# DeMux.net
KiCad netlist of a schematic drawn in EAGLE
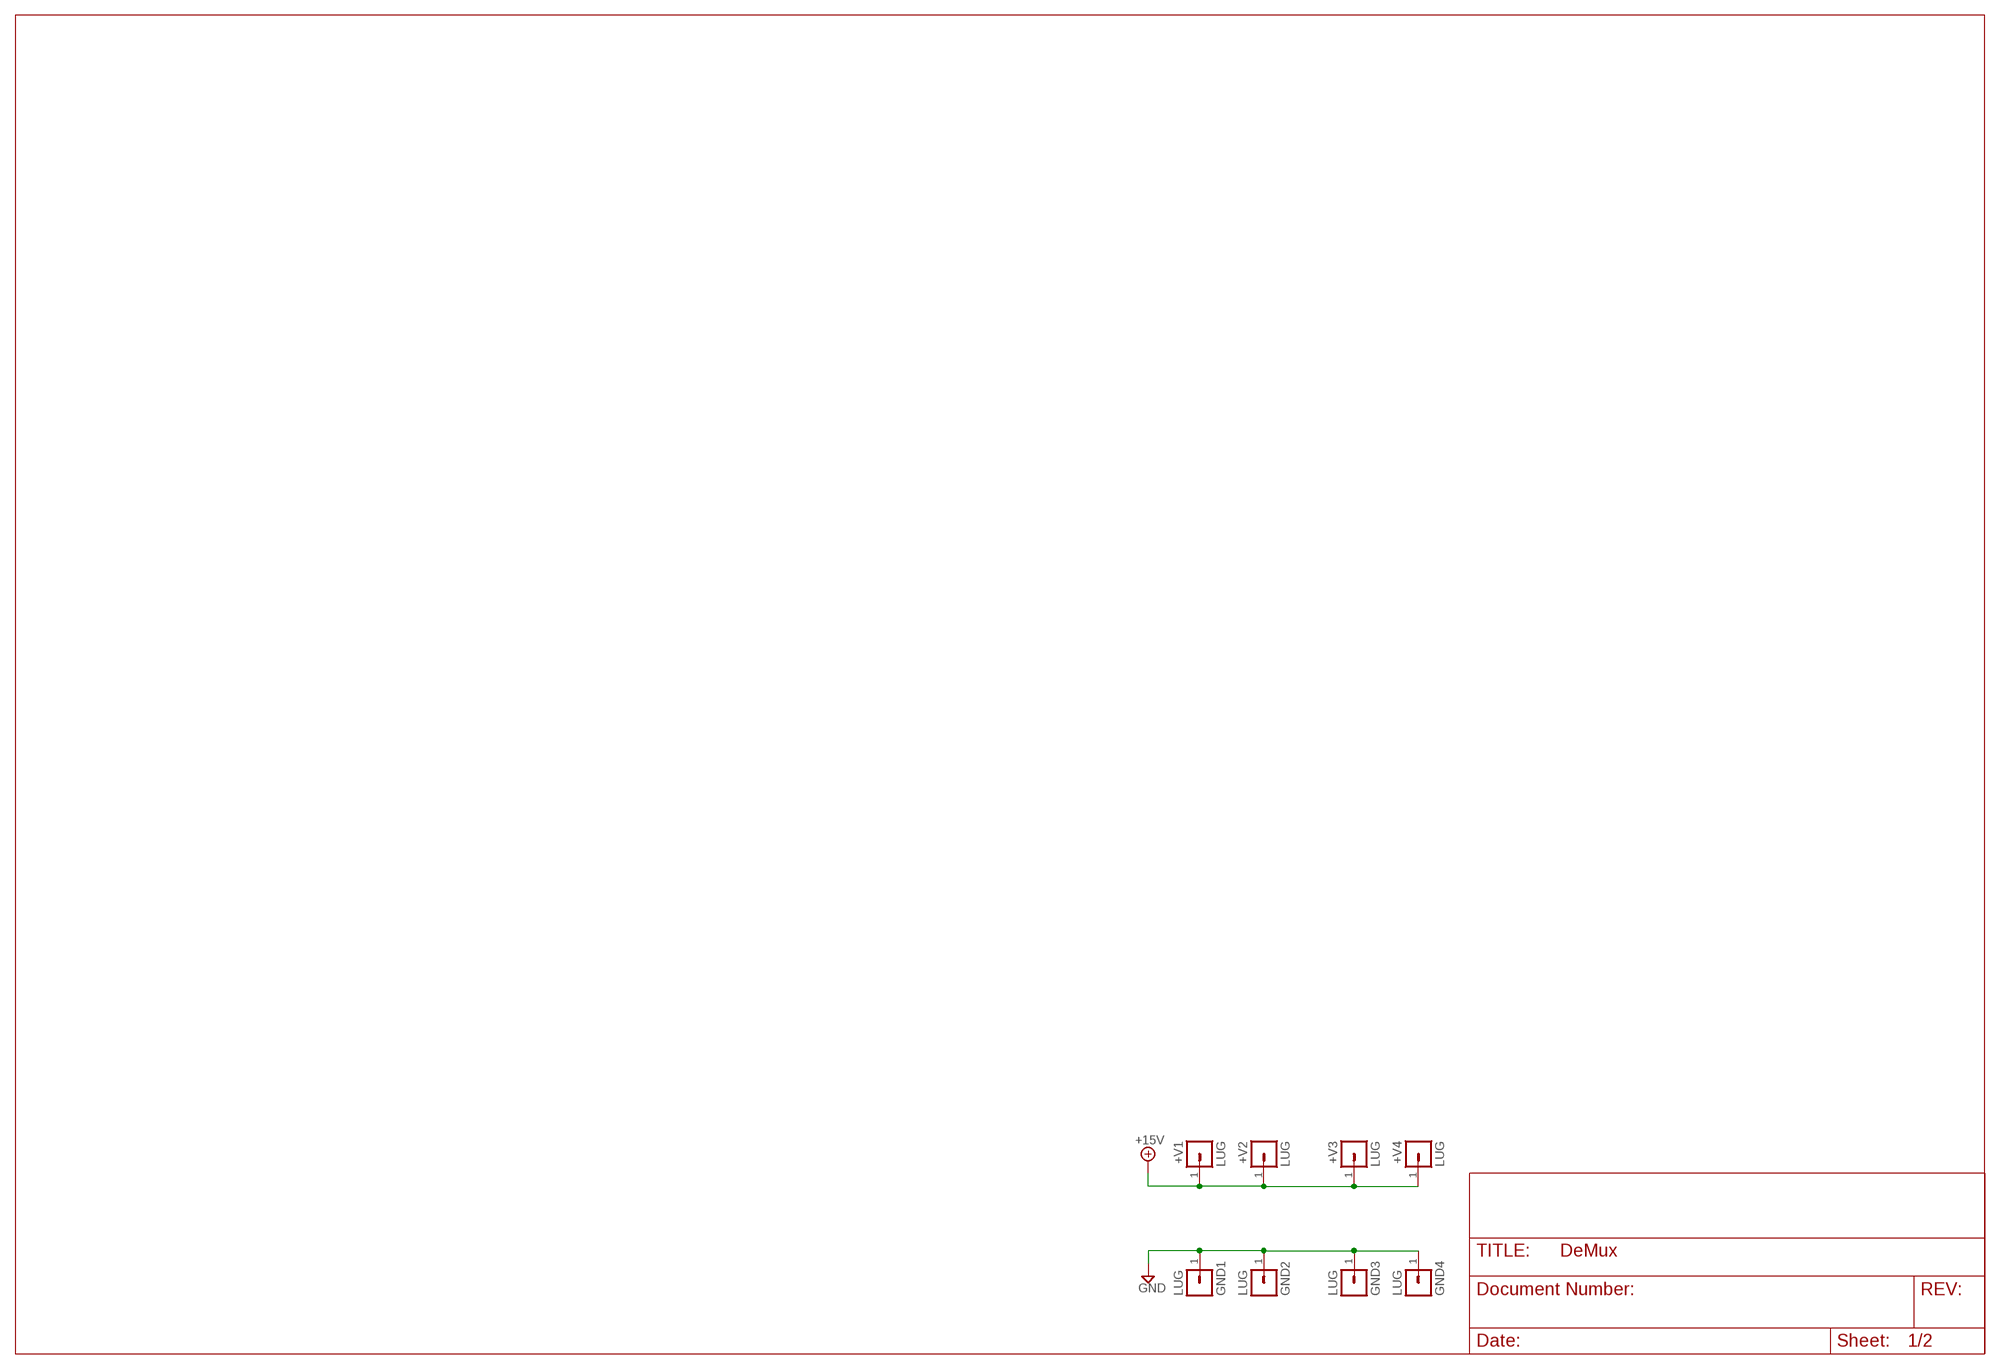
[diagram p0: schematic, sheet 1]
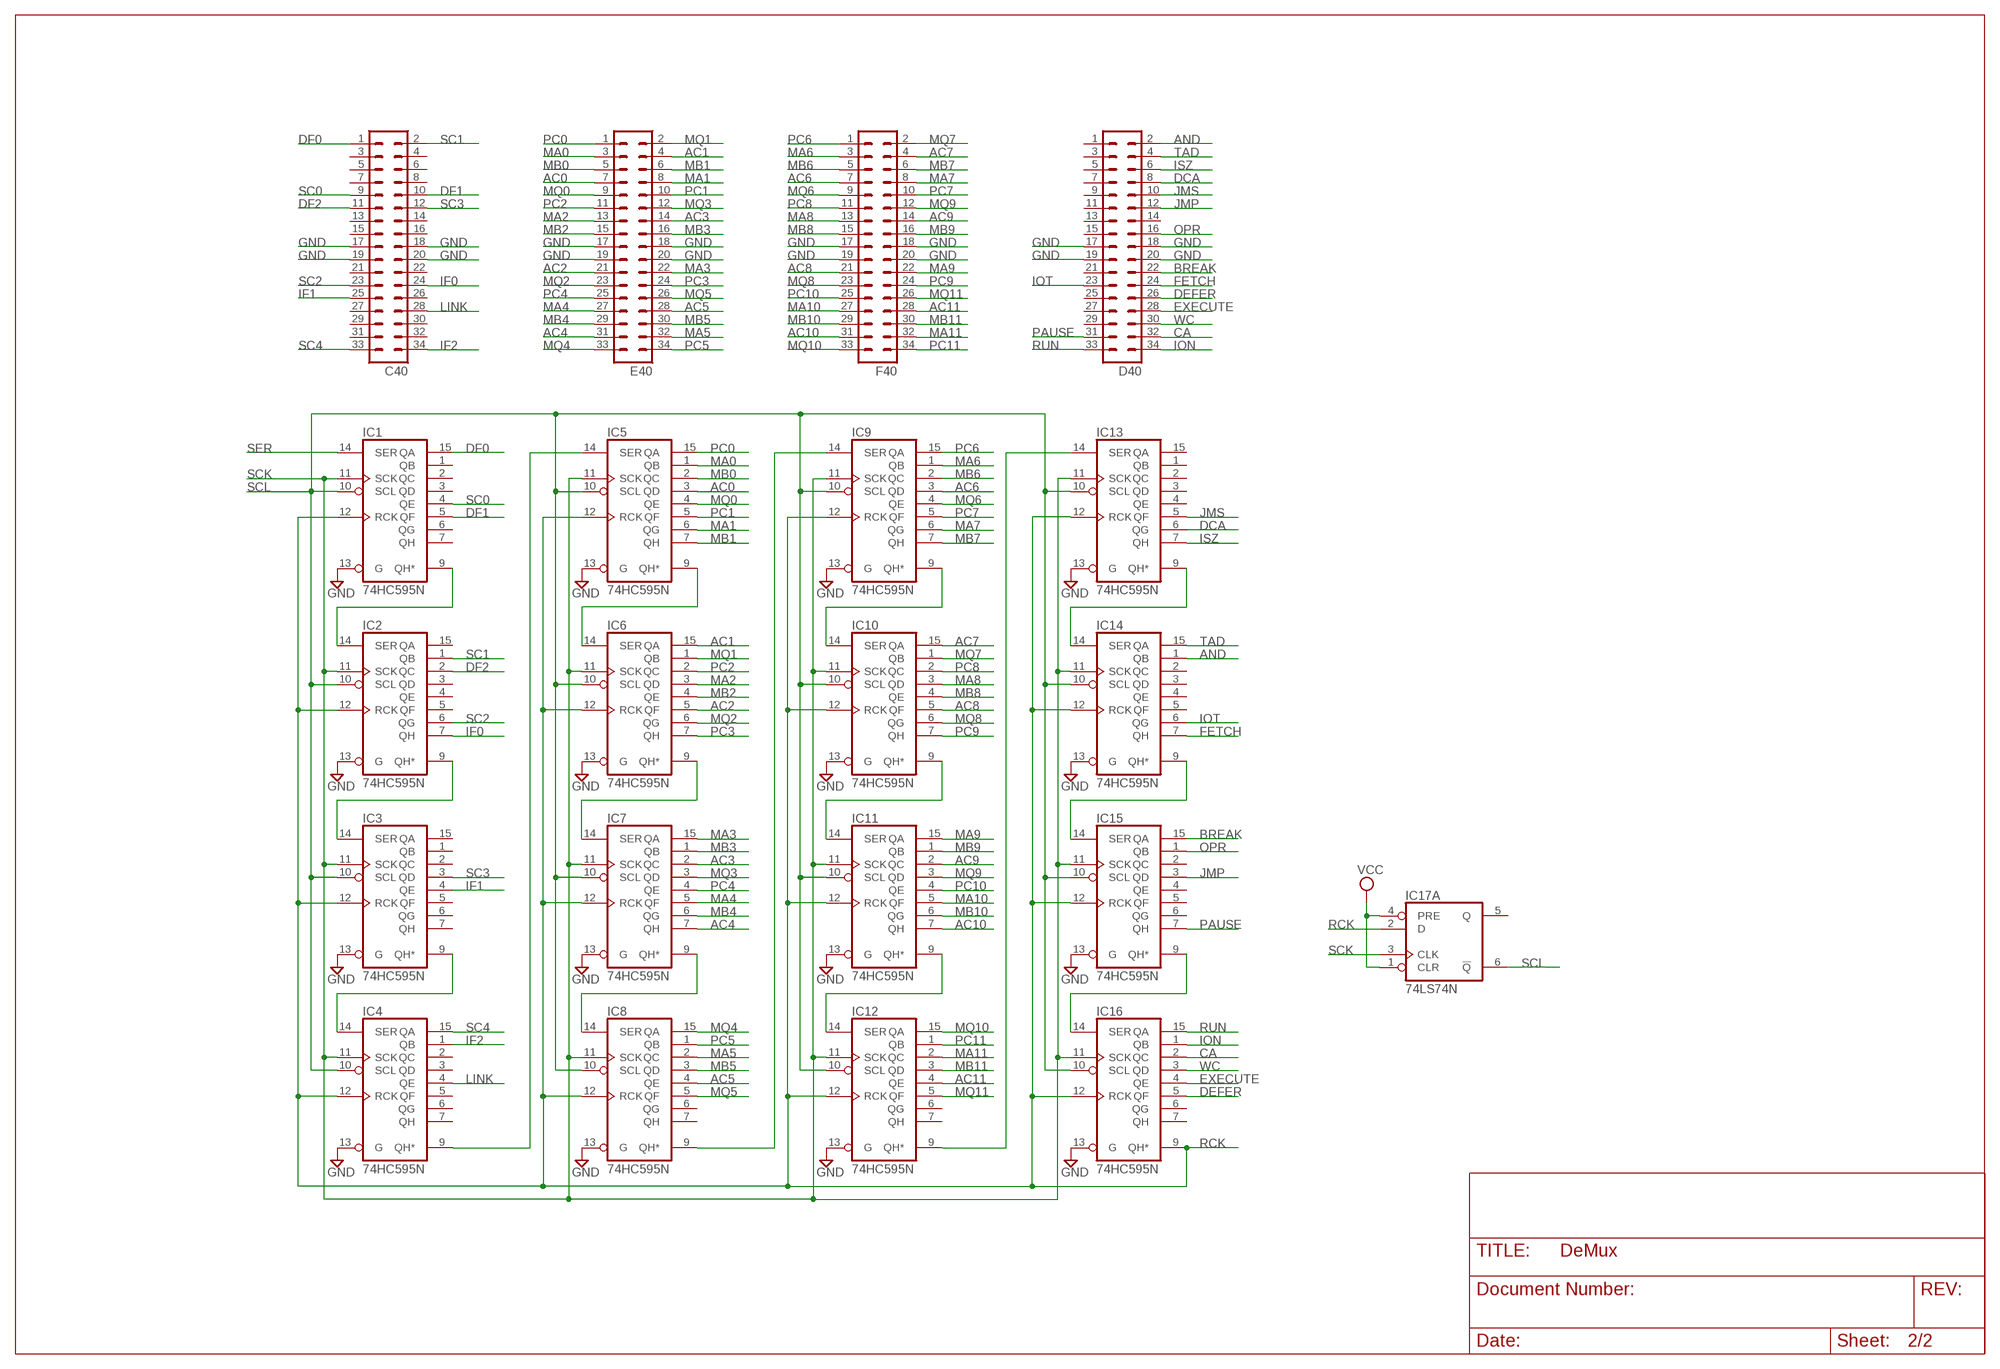
[diagram p1: schematic, sheet 2]

(export (version "E")
  (design (tool "Eeschema 10.0.6"))
  (components
    (comp (ref "+V1")
      (value "LUG")
      (footprint "eagle-import:SPADELUG")
      (libsource (lib "eagle-import") (part "LUG"))
    )
    (comp (ref "+V2")
      (value "LUG")
      (footprint "eagle-import:SPADELUG")
      (libsource (lib "eagle-import") (part "LUG"))
    )
    (comp (ref "+V3")
      (value "LUG")
      (footprint "eagle-import:SPADELUG")
      (libsource (lib "eagle-import") (part "LUG"))
    )
    (comp (ref "+V4")
      (value "LUG")
      (footprint "eagle-import:SPADELUG")
      (libsource (lib "eagle-import") (part "LUG"))
    )
    (comp (ref "GND1")
      (value "LUG")
      (footprint "eagle-import:SPADELUG")
      (libsource (lib "eagle-import") (part "LUG"))
    )
    (comp (ref "GND2")
      (value "LUG")
      (footprint "eagle-import:SPADELUG")
      (libsource (lib "eagle-import") (part "LUG"))
    )
    (comp (ref "GND3")
      (value "LUG")
      (footprint "eagle-import:SPADELUG")
      (libsource (lib "eagle-import") (part "LUG"))
    )
    (comp (ref "GND4")
      (value "LUG")
      (footprint "eagle-import:SPADELUG")
      (libsource (lib "eagle-import") (part "LUG"))
    )
    (comp (ref "C40")
      (value "MA17-2")
      (footprint "eagle-import:MA17-2")
      (libsource (lib "eagle-import") (part "MA17-2"))
    )
    (comp (ref "D40")
      (value "MA17-2")
      (footprint "eagle-import:MA17-2")
      (libsource (lib "eagle-import") (part "MA17-2"))
    )
    (comp (ref "E40")
      (value "MA17-2")
      (footprint "eagle-import:MA17-2")
      (libsource (lib "eagle-import") (part "MA17-2"))
    )
    (comp (ref "F40")
      (value "MA17-2")
      (footprint "eagle-import:MA17-2")
      (libsource (lib "eagle-import") (part "MA17-2"))
    )
    (comp (ref "IC1")
      (value "74HC595N")
      (footprint "eagle-import:DIL16")
      (libsource (lib "eagle-import") (part "74595NLS"))
    )
    (comp (ref "IC2")
      (value "74HC595N")
      (footprint "eagle-import:DIL16")
      (libsource (lib "eagle-import") (part "74595NLS"))
    )
    (comp (ref "IC3")
      (value "74HC595N")
      (footprint "eagle-import:DIL16")
      (libsource (lib "eagle-import") (part "74595NLS"))
    )
    (comp (ref "IC4")
      (value "74HC595N")
      (footprint "eagle-import:DIL16")
      (libsource (lib "eagle-import") (part "74595NLS"))
    )
    (comp (ref "IC5")
      (value "74HC595N")
      (footprint "eagle-import:DIL16")
      (libsource (lib "eagle-import") (part "74595NLS"))
    )
    (comp (ref "IC6")
      (value "74HC595N")
      (footprint "eagle-import:DIL16")
      (libsource (lib "eagle-import") (part "74595NLS"))
    )
    (comp (ref "IC7")
      (value "74HC595N")
      (footprint "eagle-import:DIL16")
      (libsource (lib "eagle-import") (part "74595NLS"))
    )
    (comp (ref "IC8")
      (value "74HC595N")
      (footprint "eagle-import:DIL16")
      (libsource (lib "eagle-import") (part "74595NLS"))
    )
    (comp (ref "IC9")
      (value "74HC595N")
      (footprint "eagle-import:DIL16")
      (libsource (lib "eagle-import") (part "74595NLS"))
    )
    (comp (ref "IC10")
      (value "74HC595N")
      (footprint "eagle-import:DIL16")
      (libsource (lib "eagle-import") (part "74595NLS"))
    )
    (comp (ref "IC11")
      (value "74HC595N")
      (footprint "eagle-import:DIL16")
      (libsource (lib "eagle-import") (part "74595NLS"))
    )
    (comp (ref "IC12")
      (value "74HC595N")
      (footprint "eagle-import:DIL16")
      (libsource (lib "eagle-import") (part "74595NLS"))
    )
    (comp (ref "IC13")
      (value "74HC595N")
      (footprint "eagle-import:DIL16")
      (libsource (lib "eagle-import") (part "74595NLS"))
    )
    (comp (ref "IC14")
      (value "74HC595N")
      (footprint "eagle-import:DIL16")
      (libsource (lib "eagle-import") (part "74595NLS"))
    )
    (comp (ref "IC15")
      (value "74HC595N")
      (footprint "eagle-import:DIL16")
      (libsource (lib "eagle-import") (part "74595NLS"))
    )
    (comp (ref "IC16")
      (value "74HC595N")
      (footprint "eagle-import:DIL16")
      (libsource (lib "eagle-import") (part "74595NLS"))
    )
    (comp (ref "IC17")
      (value "74LS74N")
      (footprint "eagle-import:DIL14")
      (libsource (lib "eagle-import") (part "7474NLS"))
    )
  )
  (nets
    (net (code "1") (name "+15V") (class "Default")
      (node (ref "+V1") (pin "1") (pinfunction "1_1") (pintype "passive"))
      (node (ref "+V2") (pin "1") (pinfunction "1_1") (pintype "passive"))
      (node (ref "+V3") (pin "1") (pinfunction "1_1") (pintype "passive"))
      (node (ref "+V4") (pin "1") (pinfunction "1_1") (pintype "passive"))
    )
    (net (code "2") (name "AC0") (class "Default")
      (node (ref "E40") (pin "7") (pinfunction "7_7") (pintype "passive"))
      (node (ref "IC5") (pin "3") (pinfunction "QD_3") (pintype "tri_state"))
    )
    (net (code "3") (name "AC1") (class "Default")
      (node (ref "E40") (pin "4") (pinfunction "4_4") (pintype "passive"))
      (node (ref "IC6") (pin "15") (pinfunction "QA_15") (pintype "tri_state"))
    )
    (net (code "4") (name "AC2") (class "Default")
      (node (ref "E40") (pin "21") (pinfunction "21_21") (pintype "passive"))
      (node (ref "IC6") (pin "5") (pinfunction "QF_5") (pintype "tri_state"))
    )
    (net (code "5") (name "AC3") (class "Default")
      (node (ref "E40") (pin "14") (pinfunction "14_14") (pintype "passive"))
      (node (ref "IC7") (pin "2") (pinfunction "QC_2") (pintype "tri_state"))
    )
    (net (code "6") (name "AC4") (class "Default")
      (node (ref "E40") (pin "31") (pinfunction "31_31") (pintype "passive"))
      (node (ref "IC7") (pin "7") (pinfunction "QH_7") (pintype "tri_state"))
    )
    (net (code "7") (name "AC5") (class "Default")
      (node (ref "E40") (pin "28") (pinfunction "28_28") (pintype "passive"))
      (node (ref "IC8") (pin "4") (pinfunction "QE_4") (pintype "tri_state"))
    )
    (net (code "8") (name "AC6") (class "Default")
      (node (ref "F40") (pin "7") (pinfunction "7_7") (pintype "passive"))
      (node (ref "IC9") (pin "3") (pinfunction "QD_3") (pintype "tri_state"))
    )
    (net (code "9") (name "AC7") (class "Default")
      (node (ref "F40") (pin "4") (pinfunction "4_4") (pintype "passive"))
      (node (ref "IC10") (pin "15") (pinfunction "QA_15") (pintype "tri_state"))
    )
    (net (code "10") (name "AC8") (class "Default")
      (node (ref "F40") (pin "21") (pinfunction "21_21") (pintype "passive"))
      (node (ref "IC10") (pin "5") (pinfunction "QF_5") (pintype "tri_state"))
    )
    (net (code "11") (name "AC9") (class "Default")
      (node (ref "F40") (pin "14") (pinfunction "14_14") (pintype "passive"))
      (node (ref "IC11") (pin "2") (pinfunction "QC_2") (pintype "tri_state"))
    )
    (net (code "12") (name "AC10") (class "Default")
      (node (ref "F40") (pin "31") (pinfunction "31_31") (pintype "passive"))
      (node (ref "IC11") (pin "7") (pinfunction "QH_7") (pintype "tri_state"))
    )
    (net (code "13") (name "AC11") (class "Default")
      (node (ref "F40") (pin "28") (pinfunction "28_28") (pintype "passive"))
      (node (ref "IC12") (pin "4") (pinfunction "QE_4") (pintype "tri_state"))
    )
    (net (code "14") (name "AND") (class "Default")
      (node (ref "D40") (pin "2") (pinfunction "2_2") (pintype "passive"))
      (node (ref "IC14") (pin "1") (pinfunction "QB_1") (pintype "tri_state"))
    )
    (net (code "15") (name "BREAK") (class "Default")
      (node (ref "D40") (pin "22") (pinfunction "22_22") (pintype "passive"))
      (node (ref "IC15") (pin "15") (pinfunction "QA_15") (pintype "tri_state"))
    )
    (net (code "16") (name "CA") (class "Default")
      (node (ref "D40") (pin "32") (pinfunction "32_32") (pintype "passive"))
      (node (ref "IC16") (pin "2") (pinfunction "QC_2") (pintype "tri_state"))
    )
    (net (code "17") (name "DCA") (class "Default")
      (node (ref "D40") (pin "8") (pinfunction "8_8") (pintype "passive"))
      (node (ref "IC13") (pin "6") (pinfunction "QG_6") (pintype "tri_state"))
    )
    (net (code "18") (name "DEFER") (class "Default")
      (node (ref "D40") (pin "26") (pinfunction "26_26") (pintype "passive"))
      (node (ref "IC16") (pin "5") (pinfunction "QF_5") (pintype "tri_state"))
    )
    (net (code "19") (name "DF0") (class "Default")
      (node (ref "C40") (pin "1") (pinfunction "1_1") (pintype "passive"))
      (node (ref "IC1") (pin "15") (pinfunction "QA_15") (pintype "tri_state"))
    )
    (net (code "20") (name "DF1") (class "Default")
      (node (ref "C40") (pin "10") (pinfunction "10_10") (pintype "passive"))
      (node (ref "IC1") (pin "5") (pinfunction "QF_5") (pintype "tri_state"))
    )
    (net (code "21") (name "DF2") (class "Default")
      (node (ref "C40") (pin "11") (pinfunction "11_11") (pintype "passive"))
      (node (ref "IC2") (pin "2") (pinfunction "QC_2") (pintype "tri_state"))
    )
    (net (code "22") (name "EXECUTE") (class "Default")
      (node (ref "D40") (pin "28") (pinfunction "28_28") (pintype "passive"))
      (node (ref "IC16") (pin "4") (pinfunction "QE_4") (pintype "tri_state"))
    )
    (net (code "23") (name "FETCH") (class "Default")
      (node (ref "D40") (pin "24") (pinfunction "24_24") (pintype "passive"))
      (node (ref "IC14") (pin "7") (pinfunction "QH_7") (pintype "tri_state"))
    )
    (net (code "24") (name "GND") (class "Default")
      (node (ref "C40") (pin "17") (pinfunction "17_17") (pintype "passive"))
      (node (ref "C40") (pin "18") (pinfunction "18_18") (pintype "passive"))
      (node (ref "C40") (pin "19") (pinfunction "19_19") (pintype "passive"))
      (node (ref "C40") (pin "20") (pinfunction "20_20") (pintype "passive"))
      (node (ref "D40") (pin "17") (pinfunction "17_17") (pintype "passive"))
      (node (ref "D40") (pin "18") (pinfunction "18_18") (pintype "passive"))
      (node (ref "D40") (pin "19") (pinfunction "19_19") (pintype "passive"))
      (node (ref "D40") (pin "20") (pinfunction "20_20") (pintype "passive"))
      (node (ref "E40") (pin "17") (pinfunction "17_17") (pintype "passive"))
      (node (ref "E40") (pin "18") (pinfunction "18_18") (pintype "passive"))
      (node (ref "E40") (pin "19") (pinfunction "19_19") (pintype "passive"))
      (node (ref "E40") (pin "20") (pinfunction "20_20") (pintype "passive"))
      (node (ref "F40") (pin "17") (pinfunction "17_17") (pintype "passive"))
      (node (ref "F40") (pin "18") (pinfunction "18_18") (pintype "passive"))
      (node (ref "F40") (pin "19") (pinfunction "19_19") (pintype "passive"))
      (node (ref "F40") (pin "20") (pinfunction "20_20") (pintype "passive"))
      (node (ref "GND1") (pin "1") (pinfunction "1_1") (pintype "passive"))
      (node (ref "GND2") (pin "1") (pinfunction "1_1") (pintype "passive"))
      (node (ref "GND3") (pin "1") (pinfunction "1_1") (pintype "passive"))
      (node (ref "GND4") (pin "1") (pinfunction "1_1") (pintype "passive"))
      (node (ref "IC1") (pin "13") (pinfunction "G_13") (pintype "input"))
      (node (ref "IC10") (pin "13") (pinfunction "G_13") (pintype "input"))
      (node (ref "IC11") (pin "13") (pinfunction "G_13") (pintype "input"))
      (node (ref "IC12") (pin "13") (pinfunction "G_13") (pintype "input"))
      (node (ref "IC13") (pin "13") (pinfunction "G_13") (pintype "input"))
      (node (ref "IC14") (pin "13") (pinfunction "G_13") (pintype "input"))
      (node (ref "IC15") (pin "13") (pinfunction "G_13") (pintype "input"))
      (node (ref "IC16") (pin "13") (pinfunction "G_13") (pintype "input"))
      (node (ref "IC2") (pin "13") (pinfunction "G_13") (pintype "input"))
      (node (ref "IC3") (pin "13") (pinfunction "G_13") (pintype "input"))
      (node (ref "IC4") (pin "13") (pinfunction "G_13") (pintype "input"))
      (node (ref "IC5") (pin "13") (pinfunction "G_13") (pintype "input"))
      (node (ref "IC6") (pin "13") (pinfunction "G_13") (pintype "input"))
      (node (ref "IC7") (pin "13") (pinfunction "G_13") (pintype "input"))
      (node (ref "IC8") (pin "13") (pinfunction "G_13") (pintype "input"))
      (node (ref "IC9") (pin "13") (pinfunction "G_13") (pintype "input"))
    )
    (net (code "25") (name "IF0") (class "Default")
      (node (ref "C40") (pin "24") (pinfunction "24_24") (pintype "passive"))
      (node (ref "IC2") (pin "7") (pinfunction "QH_7") (pintype "tri_state"))
    )
    (net (code "26") (name "IF1") (class "Default")
      (node (ref "C40") (pin "25") (pinfunction "25_25") (pintype "passive"))
      (node (ref "IC3") (pin "4") (pinfunction "QE_4") (pintype "tri_state"))
    )
    (net (code "27") (name "IF2") (class "Default")
      (node (ref "C40") (pin "34") (pinfunction "34_34") (pintype "passive"))
      (node (ref "IC4") (pin "1") (pinfunction "QB_1") (pintype "tri_state"))
    )
    (net (code "28") (name "ION") (class "Default")
      (node (ref "D40") (pin "34") (pinfunction "34_34") (pintype "passive"))
      (node (ref "IC16") (pin "1") (pinfunction "QB_1") (pintype "tri_state"))
    )
    (net (code "29") (name "IOT") (class "Default")
      (node (ref "D40") (pin "23") (pinfunction "23_23") (pintype "passive"))
      (node (ref "IC14") (pin "6") (pinfunction "QG_6") (pintype "tri_state"))
    )
    (net (code "30") (name "ISZ") (class "Default")
      (node (ref "D40") (pin "6") (pinfunction "6_6") (pintype "passive"))
      (node (ref "IC13") (pin "7") (pinfunction "QH_7") (pintype "tri_state"))
    )
    (net (code "31") (name "JMP") (class "Default")
      (node (ref "D40") (pin "12") (pinfunction "12_12") (pintype "passive"))
      (node (ref "IC15") (pin "3") (pinfunction "QD_3") (pintype "tri_state"))
    )
    (net (code "32") (name "JMS") (class "Default")
      (node (ref "D40") (pin "10") (pinfunction "10_10") (pintype "passive"))
      (node (ref "IC13") (pin "5") (pinfunction "QF_5") (pintype "tri_state"))
    )
    (net (code "33") (name "LINK") (class "Default")
      (node (ref "C40") (pin "28") (pinfunction "28_28") (pintype "passive"))
      (node (ref "IC4") (pin "4") (pinfunction "QE_4") (pintype "tri_state"))
    )
    (net (code "34") (name "MA0") (class "Default")
      (node (ref "E40") (pin "3") (pinfunction "3_3") (pintype "passive"))
      (node (ref "IC5") (pin "1") (pinfunction "QB_1") (pintype "tri_state"))
    )
    (net (code "35") (name "MA1") (class "Default")
      (node (ref "E40") (pin "8") (pinfunction "8_8") (pintype "passive"))
      (node (ref "IC5") (pin "6") (pinfunction "QG_6") (pintype "tri_state"))
    )
    (net (code "36") (name "MA2") (class "Default")
      (node (ref "E40") (pin "13") (pinfunction "13_13") (pintype "passive"))
      (node (ref "IC6") (pin "3") (pinfunction "QD_3") (pintype "tri_state"))
    )
    (net (code "37") (name "MA3") (class "Default")
      (node (ref "E40") (pin "22") (pinfunction "22_22") (pintype "passive"))
      (node (ref "IC7") (pin "15") (pinfunction "QA_15") (pintype "tri_state"))
    )
    (net (code "38") (name "MA4") (class "Default")
      (node (ref "E40") (pin "27") (pinfunction "27_27") (pintype "passive"))
      (node (ref "IC7") (pin "5") (pinfunction "QF_5") (pintype "tri_state"))
    )
    (net (code "39") (name "MA5") (class "Default")
      (node (ref "E40") (pin "32") (pinfunction "32_32") (pintype "passive"))
      (node (ref "IC8") (pin "2") (pinfunction "QC_2") (pintype "tri_state"))
    )
    (net (code "40") (name "MA6") (class "Default")
      (node (ref "F40") (pin "3") (pinfunction "3_3") (pintype "passive"))
      (node (ref "IC9") (pin "1") (pinfunction "QB_1") (pintype "tri_state"))
    )
    (net (code "41") (name "MA7") (class "Default")
      (node (ref "F40") (pin "8") (pinfunction "8_8") (pintype "passive"))
      (node (ref "IC9") (pin "6") (pinfunction "QG_6") (pintype "tri_state"))
    )
    (net (code "42") (name "MA8") (class "Default")
      (node (ref "F40") (pin "13") (pinfunction "13_13") (pintype "passive"))
      (node (ref "IC10") (pin "3") (pinfunction "QD_3") (pintype "tri_state"))
    )
    (net (code "43") (name "MA9") (class "Default")
      (node (ref "F40") (pin "22") (pinfunction "22_22") (pintype "passive"))
      (node (ref "IC11") (pin "15") (pinfunction "QA_15") (pintype "tri_state"))
    )
    (net (code "44") (name "MA10") (class "Default")
      (node (ref "F40") (pin "27") (pinfunction "27_27") (pintype "passive"))
      (node (ref "IC11") (pin "5") (pinfunction "QF_5") (pintype "tri_state"))
    )
    (net (code "45") (name "MA11") (class "Default")
      (node (ref "F40") (pin "32") (pinfunction "32_32") (pintype "passive"))
      (node (ref "IC12") (pin "2") (pinfunction "QC_2") (pintype "tri_state"))
    )
    (net (code "46") (name "MB0") (class "Default")
      (node (ref "E40") (pin "5") (pinfunction "5_5") (pintype "passive"))
      (node (ref "IC5") (pin "2") (pinfunction "QC_2") (pintype "tri_state"))
    )
    (net (code "47") (name "MB1") (class "Default")
      (node (ref "E40") (pin "6") (pinfunction "6_6") (pintype "passive"))
      (node (ref "IC5") (pin "7") (pinfunction "QH_7") (pintype "tri_state"))
    )
    (net (code "48") (name "MB2") (class "Default")
      (node (ref "E40") (pin "15") (pinfunction "15_15") (pintype "passive"))
      (node (ref "IC6") (pin "4") (pinfunction "QE_4") (pintype "tri_state"))
    )
    (net (code "49") (name "MB3") (class "Default")
      (node (ref "E40") (pin "16") (pinfunction "16_16") (pintype "passive"))
      (node (ref "IC7") (pin "1") (pinfunction "QB_1") (pintype "tri_state"))
    )
    (net (code "50") (name "MB4") (class "Default")
      (node (ref "E40") (pin "29") (pinfunction "29_29") (pintype "passive"))
      (node (ref "IC7") (pin "6") (pinfunction "QG_6") (pintype "tri_state"))
    )
    (net (code "51") (name "MB5") (class "Default")
      (node (ref "E40") (pin "30") (pinfunction "30_30") (pintype "passive"))
      (node (ref "IC8") (pin "3") (pinfunction "QD_3") (pintype "tri_state"))
    )
    (net (code "52") (name "MB6") (class "Default")
      (node (ref "F40") (pin "5") (pinfunction "5_5") (pintype "passive"))
      (node (ref "IC9") (pin "2") (pinfunction "QC_2") (pintype "tri_state"))
    )
    (net (code "53") (name "MB7") (class "Default")
      (node (ref "F40") (pin "6") (pinfunction "6_6") (pintype "passive"))
      (node (ref "IC9") (pin "7") (pinfunction "QH_7") (pintype "tri_state"))
    )
    (net (code "54") (name "MB8") (class "Default")
      (node (ref "F40") (pin "15") (pinfunction "15_15") (pintype "passive"))
      (node (ref "IC10") (pin "4") (pinfunction "QE_4") (pintype "tri_state"))
    )
    (net (code "55") (name "MB9") (class "Default")
      (node (ref "F40") (pin "16") (pinfunction "16_16") (pintype "passive"))
      (node (ref "IC11") (pin "1") (pinfunction "QB_1") (pintype "tri_state"))
    )
    (net (code "56") (name "MB10") (class "Default")
      (node (ref "F40") (pin "29") (pinfunction "29_29") (pintype "passive"))
      (node (ref "IC11") (pin "6") (pinfunction "QG_6") (pintype "tri_state"))
    )
    (net (code "57") (name "MB11") (class "Default")
      (node (ref "F40") (pin "30") (pinfunction "30_30") (pintype "passive"))
      (node (ref "IC12") (pin "3") (pinfunction "QD_3") (pintype "tri_state"))
    )
    (net (code "58") (name "MQ0") (class "Default")
      (node (ref "E40") (pin "9") (pinfunction "9_9") (pintype "passive"))
      (node (ref "IC5") (pin "4") (pinfunction "QE_4") (pintype "tri_state"))
    )
    (net (code "59") (name "MQ1") (class "Default")
      (node (ref "E40") (pin "2") (pinfunction "2_2") (pintype "passive"))
      (node (ref "IC6") (pin "1") (pinfunction "QB_1") (pintype "tri_state"))
    )
    (net (code "60") (name "MQ2") (class "Default")
      (node (ref "E40") (pin "23") (pinfunction "23_23") (pintype "passive"))
      (node (ref "IC6") (pin "6") (pinfunction "QG_6") (pintype "tri_state"))
    )
    (net (code "61") (name "MQ3") (class "Default")
      (node (ref "E40") (pin "12") (pinfunction "12_12") (pintype "passive"))
      (node (ref "IC7") (pin "3") (pinfunction "QD_3") (pintype "tri_state"))
    )
    (net (code "62") (name "MQ4") (class "Default")
      (node (ref "E40") (pin "33") (pinfunction "33_33") (pintype "passive"))
      (node (ref "IC8") (pin "15") (pinfunction "QA_15") (pintype "tri_state"))
    )
    (net (code "63") (name "MQ5") (class "Default")
      (node (ref "E40") (pin "26") (pinfunction "26_26") (pintype "passive"))
      (node (ref "IC8") (pin "5") (pinfunction "QF_5") (pintype "tri_state"))
    )
    (net (code "64") (name "MQ6") (class "Default")
      (node (ref "F40") (pin "9") (pinfunction "9_9") (pintype "passive"))
      (node (ref "IC9") (pin "4") (pinfunction "QE_4") (pintype "tri_state"))
    )
    (net (code "65") (name "MQ7") (class "Default")
      (node (ref "F40") (pin "2") (pinfunction "2_2") (pintype "passive"))
      (node (ref "IC10") (pin "1") (pinfunction "QB_1") (pintype "tri_state"))
    )
    (net (code "66") (name "MQ8") (class "Default")
      (node (ref "F40") (pin "23") (pinfunction "23_23") (pintype "passive"))
      (node (ref "IC10") (pin "6") (pinfunction "QG_6") (pintype "tri_state"))
    )
    (net (code "67") (name "MQ9") (class "Default")
      (node (ref "F40") (pin "12") (pinfunction "12_12") (pintype "passive"))
      (node (ref "IC11") (pin "3") (pinfunction "QD_3") (pintype "tri_state"))
    )
    (net (code "68") (name "MQ10") (class "Default")
      (node (ref "F40") (pin "33") (pinfunction "33_33") (pintype "passive"))
      (node (ref "IC12") (pin "15") (pinfunction "QA_15") (pintype "tri_state"))
    )
    (net (code "69") (name "MQ11") (class "Default")
      (node (ref "F40") (pin "26") (pinfunction "26_26") (pintype "passive"))
      (node (ref "IC12") (pin "5") (pinfunction "QF_5") (pintype "tri_state"))
    )
    (net (code "70") (name "Net-(IC1A-QH*)") (class "Default")
      (node (ref "IC1") (pin "9") (pinfunction "QH*_9") (pintype "tri_state"))
      (node (ref "IC2") (pin "14") (pinfunction "SER_14") (pintype "input"))
    )
    (net (code "71") (name "Net-(IC2A-QH*)") (class "Default")
      (node (ref "IC2") (pin "9") (pinfunction "QH*_9") (pintype "tri_state"))
      (node (ref "IC3") (pin "14") (pinfunction "SER_14") (pintype "input"))
    )
    (net (code "72") (name "Net-(IC3A-QH*)") (class "Default")
      (node (ref "IC3") (pin "9") (pinfunction "QH*_9") (pintype "tri_state"))
      (node (ref "IC4") (pin "14") (pinfunction "SER_14") (pintype "input"))
    )
    (net (code "73") (name "Net-(IC4A-QH*)") (class "Default")
      (node (ref "IC4") (pin "9") (pinfunction "QH*_9") (pintype "tri_state"))
      (node (ref "IC5") (pin "14") (pinfunction "SER_14") (pintype "input"))
    )
    (net (code "74") (name "Net-(IC5A-QH*)") (class "Default")
      (node (ref "IC5") (pin "9") (pinfunction "QH*_9") (pintype "tri_state"))
      (node (ref "IC6") (pin "14") (pinfunction "SER_14") (pintype "input"))
    )
    (net (code "75") (name "Net-(IC6A-QH*)") (class "Default")
      (node (ref "IC6") (pin "9") (pinfunction "QH*_9") (pintype "tri_state"))
      (node (ref "IC7") (pin "14") (pinfunction "SER_14") (pintype "input"))
    )
    (net (code "76") (name "Net-(IC7A-QH*)") (class "Default")
      (node (ref "IC7") (pin "9") (pinfunction "QH*_9") (pintype "tri_state"))
      (node (ref "IC8") (pin "14") (pinfunction "SER_14") (pintype "input"))
    )
    (net (code "77") (name "Net-(IC8A-QH*)") (class "Default")
      (node (ref "IC8") (pin "9") (pinfunction "QH*_9") (pintype "tri_state"))
      (node (ref "IC9") (pin "14") (pinfunction "SER_14") (pintype "input"))
    )
    (net (code "78") (name "Net-(IC10A-QH*)") (class "Default")
      (node (ref "IC10") (pin "9") (pinfunction "QH*_9") (pintype "tri_state"))
      (node (ref "IC11") (pin "14") (pinfunction "SER_14") (pintype "input"))
    )
    (net (code "79") (name "Net-(IC10A-SER)") (class "Default")
      (node (ref "IC10") (pin "14") (pinfunction "SER_14") (pintype "input"))
      (node (ref "IC9") (pin "9") (pinfunction "QH*_9") (pintype "tri_state"))
    )
    (net (code "80") (name "Net-(IC11A-QH*)") (class "Default")
      (node (ref "IC11") (pin "9") (pinfunction "QH*_9") (pintype "tri_state"))
      (node (ref "IC12") (pin "14") (pinfunction "SER_14") (pintype "input"))
    )
    (net (code "81") (name "Net-(IC12A-QH*)") (class "Default")
      (node (ref "IC12") (pin "9") (pinfunction "QH*_9") (pintype "tri_state"))
      (node (ref "IC13") (pin "14") (pinfunction "SER_14") (pintype "input"))
    )
    (net (code "82") (name "Net-(IC13A-QH*)") (class "Default")
      (node (ref "IC13") (pin "9") (pinfunction "QH*_9") (pintype "tri_state"))
      (node (ref "IC14") (pin "14") (pinfunction "SER_14") (pintype "input"))
    )
    (net (code "83") (name "Net-(IC14A-QH*)") (class "Default")
      (node (ref "IC14") (pin "9") (pinfunction "QH*_9") (pintype "tri_state"))
      (node (ref "IC15") (pin "14") (pinfunction "SER_14") (pintype "input"))
    )
    (net (code "84") (name "Net-(IC15A-QH*)") (class "Default")
      (node (ref "IC15") (pin "9") (pinfunction "QH*_9") (pintype "tri_state"))
      (node (ref "IC16") (pin "14") (pinfunction "SER_14") (pintype "input"))
    )
    (net (code "85") (name "OPR") (class "Default")
      (node (ref "D40") (pin "16") (pinfunction "16_16") (pintype "passive"))
      (node (ref "IC15") (pin "1") (pinfunction "QB_1") (pintype "tri_state"))
    )
    (net (code "86") (name "PAUSE") (class "Default")
      (node (ref "D40") (pin "31") (pinfunction "31_31") (pintype "passive"))
      (node (ref "IC15") (pin "7") (pinfunction "QH_7") (pintype "tri_state"))
    )
    (net (code "87") (name "PC0") (class "Default")
      (node (ref "E40") (pin "1") (pinfunction "1_1") (pintype "passive"))
      (node (ref "IC5") (pin "15") (pinfunction "QA_15") (pintype "tri_state"))
    )
    (net (code "88") (name "PC1") (class "Default")
      (node (ref "E40") (pin "10") (pinfunction "10_10") (pintype "passive"))
      (node (ref "IC5") (pin "5") (pinfunction "QF_5") (pintype "tri_state"))
    )
    (net (code "89") (name "PC2") (class "Default")
      (node (ref "E40") (pin "11") (pinfunction "11_11") (pintype "passive"))
      (node (ref "IC6") (pin "2") (pinfunction "QC_2") (pintype "tri_state"))
    )
    (net (code "90") (name "PC3") (class "Default")
      (node (ref "E40") (pin "24") (pinfunction "24_24") (pintype "passive"))
      (node (ref "IC6") (pin "7") (pinfunction "QH_7") (pintype "tri_state"))
    )
    (net (code "91") (name "PC4") (class "Default")
      (node (ref "E40") (pin "25") (pinfunction "25_25") (pintype "passive"))
      (node (ref "IC7") (pin "4") (pinfunction "QE_4") (pintype "tri_state"))
    )
    (net (code "92") (name "PC5") (class "Default")
      (node (ref "E40") (pin "34") (pinfunction "34_34") (pintype "passive"))
      (node (ref "IC8") (pin "1") (pinfunction "QB_1") (pintype "tri_state"))
    )
    (net (code "93") (name "PC6") (class "Default")
      (node (ref "F40") (pin "1") (pinfunction "1_1") (pintype "passive"))
      (node (ref "IC9") (pin "15") (pinfunction "QA_15") (pintype "tri_state"))
    )
    (net (code "94") (name "PC7") (class "Default")
      (node (ref "F40") (pin "10") (pinfunction "10_10") (pintype "passive"))
      (node (ref "IC9") (pin "5") (pinfunction "QF_5") (pintype "tri_state"))
    )
    (net (code "95") (name "PC8") (class "Default")
      (node (ref "F40") (pin "11") (pinfunction "11_11") (pintype "passive"))
      (node (ref "IC10") (pin "2") (pinfunction "QC_2") (pintype "tri_state"))
    )
    (net (code "96") (name "PC9") (class "Default")
      (node (ref "F40") (pin "24") (pinfunction "24_24") (pintype "passive"))
      (node (ref "IC10") (pin "7") (pinfunction "QH_7") (pintype "tri_state"))
    )
    (net (code "97") (name "PC10") (class "Default")
      (node (ref "F40") (pin "25") (pinfunction "25_25") (pintype "passive"))
      (node (ref "IC11") (pin "4") (pinfunction "QE_4") (pintype "tri_state"))
    )
    (net (code "98") (name "PC11") (class "Default")
      (node (ref "F40") (pin "34") (pinfunction "34_34") (pintype "passive"))
      (node (ref "IC12") (pin "1") (pinfunction "QB_1") (pintype "tri_state"))
    )
    (net (code "99") (name "RCK") (class "Default")
      (node (ref "IC1") (pin "12") (pinfunction "RCK_12") (pintype "input"))
      (node (ref "IC10") (pin "12") (pinfunction "RCK_12") (pintype "input"))
      (node (ref "IC11") (pin "12") (pinfunction "RCK_12") (pintype "input"))
      (node (ref "IC12") (pin "12") (pinfunction "RCK_12") (pintype "input"))
      (node (ref "IC13") (pin "12") (pinfunction "RCK_12") (pintype "input"))
      (node (ref "IC14") (pin "12") (pinfunction "RCK_12") (pintype "input"))
      (node (ref "IC15") (pin "12") (pinfunction "RCK_12") (pintype "input"))
      (node (ref "IC16") (pin "12") (pinfunction "RCK_12") (pintype "input"))
      (node (ref "IC16") (pin "9") (pinfunction "QH*_9") (pintype "tri_state"))
      (node (ref "IC17") (pin "2") (pinfunction "D_2") (pintype "input"))
      (node (ref "IC2") (pin "12") (pinfunction "RCK_12") (pintype "input"))
      (node (ref "IC3") (pin "12") (pinfunction "RCK_12") (pintype "input"))
      (node (ref "IC4") (pin "12") (pinfunction "RCK_12") (pintype "input"))
      (node (ref "IC5") (pin "12") (pinfunction "RCK_12") (pintype "input"))
      (node (ref "IC6") (pin "12") (pinfunction "RCK_12") (pintype "input"))
      (node (ref "IC7") (pin "12") (pinfunction "RCK_12") (pintype "input"))
      (node (ref "IC8") (pin "12") (pinfunction "RCK_12") (pintype "input"))
      (node (ref "IC9") (pin "12") (pinfunction "RCK_12") (pintype "input"))
    )
    (net (code "100") (name "RUN") (class "Default")
      (node (ref "D40") (pin "33") (pinfunction "33_33") (pintype "passive"))
      (node (ref "IC16") (pin "15") (pinfunction "QA_15") (pintype "tri_state"))
    )
    (net (code "101") (name "SC0") (class "Default")
      (node (ref "C40") (pin "9") (pinfunction "9_9") (pintype "passive"))
      (node (ref "IC1") (pin "4") (pinfunction "QE_4") (pintype "tri_state"))
    )
    (net (code "102") (name "SC1") (class "Default")
      (node (ref "C40") (pin "2") (pinfunction "2_2") (pintype "passive"))
      (node (ref "IC2") (pin "1") (pinfunction "QB_1") (pintype "tri_state"))
    )
    (net (code "103") (name "SC2") (class "Default")
      (node (ref "C40") (pin "23") (pinfunction "23_23") (pintype "passive"))
      (node (ref "IC2") (pin "6") (pinfunction "QG_6") (pintype "tri_state"))
    )
    (net (code "104") (name "SC3") (class "Default")
      (node (ref "C40") (pin "12") (pinfunction "12_12") (pintype "passive"))
      (node (ref "IC3") (pin "3") (pinfunction "QD_3") (pintype "tri_state"))
    )
    (net (code "105") (name "SC4") (class "Default")
      (node (ref "C40") (pin "33") (pinfunction "33_33") (pintype "passive"))
      (node (ref "IC4") (pin "15") (pinfunction "QA_15") (pintype "tri_state"))
    )
    (net (code "106") (name "SCK") (class "Default")
      (node (ref "IC1") (pin "11") (pinfunction "SCK_11") (pintype "input"))
      (node (ref "IC10") (pin "11") (pinfunction "SCK_11") (pintype "input"))
      (node (ref "IC11") (pin "11") (pinfunction "SCK_11") (pintype "input"))
      (node (ref "IC12") (pin "11") (pinfunction "SCK_11") (pintype "input"))
      (node (ref "IC13") (pin "11") (pinfunction "SCK_11") (pintype "input"))
      (node (ref "IC14") (pin "11") (pinfunction "SCK_11") (pintype "input"))
      (node (ref "IC15") (pin "11") (pinfunction "SCK_11") (pintype "input"))
      (node (ref "IC16") (pin "11") (pinfunction "SCK_11") (pintype "input"))
      (node (ref "IC17") (pin "3") (pinfunction "CLK_3") (pintype "input"))
      (node (ref "IC2") (pin "11") (pinfunction "SCK_11") (pintype "input"))
      (node (ref "IC3") (pin "11") (pinfunction "SCK_11") (pintype "input"))
      (node (ref "IC4") (pin "11") (pinfunction "SCK_11") (pintype "input"))
      (node (ref "IC5") (pin "11") (pinfunction "SCK_11") (pintype "input"))
      (node (ref "IC6") (pin "11") (pinfunction "SCK_11") (pintype "input"))
      (node (ref "IC7") (pin "11") (pinfunction "SCK_11") (pintype "input"))
      (node (ref "IC8") (pin "11") (pinfunction "SCK_11") (pintype "input"))
      (node (ref "IC9") (pin "11") (pinfunction "SCK_11") (pintype "input"))
    )
    (net (code "107") (name "SCL") (class "Default")
      (node (ref "IC1") (pin "10") (pinfunction "SCL_10") (pintype "input"))
      (node (ref "IC10") (pin "10") (pinfunction "SCL_10") (pintype "input"))
      (node (ref "IC11") (pin "10") (pinfunction "SCL_10") (pintype "input"))
      (node (ref "IC12") (pin "10") (pinfunction "SCL_10") (pintype "input"))
      (node (ref "IC13") (pin "10") (pinfunction "SCL_10") (pintype "input"))
      (node (ref "IC14") (pin "10") (pinfunction "SCL_10") (pintype "input"))
      (node (ref "IC15") (pin "10") (pinfunction "SCL_10") (pintype "input"))
      (node (ref "IC16") (pin "10") (pinfunction "SCL_10") (pintype "input"))
      (node (ref "IC17") (pin "6") (pinfunction "~{Q}_6") (pintype "output"))
      (node (ref "IC2") (pin "10") (pinfunction "SCL_10") (pintype "input"))
      (node (ref "IC3") (pin "10") (pinfunction "SCL_10") (pintype "input"))
      (node (ref "IC4") (pin "10") (pinfunction "SCL_10") (pintype "input"))
      (node (ref "IC5") (pin "10") (pinfunction "SCL_10") (pintype "input"))
      (node (ref "IC6") (pin "10") (pinfunction "SCL_10") (pintype "input"))
      (node (ref "IC7") (pin "10") (pinfunction "SCL_10") (pintype "input"))
      (node (ref "IC8") (pin "10") (pinfunction "SCL_10") (pintype "input"))
      (node (ref "IC9") (pin "10") (pinfunction "SCL_10") (pintype "input"))
    )
    (net (code "108") (name "SER") (class "Default")
      (node (ref "IC1") (pin "14") (pinfunction "SER_14") (pintype "input"))
    )
    (net (code "109") (name "TAD") (class "Default")
      (node (ref "D40") (pin "4") (pinfunction "4_4") (pintype "passive"))
      (node (ref "IC14") (pin "15") (pinfunction "QA_15") (pintype "tri_state"))
    )
    (net (code "110") (name "VCC") (class "Default")
      (node (ref "IC17") (pin "1") (pinfunction "CLR_1") (pintype "input"))
      (node (ref "IC17") (pin "4") (pinfunction "PRE_4") (pintype "input"))
    )
    (net (code "111") (name "WC") (class "Default")
      (node (ref "D40") (pin "30") (pinfunction "30_30") (pintype "passive"))
      (node (ref "IC16") (pin "3") (pinfunction "QD_3") (pintype "tri_state"))
    )
    (net (code "112") (name "unconnected-(C40-Pad3)") (class "Default")
      (node (ref "C40") (pin "3") (pinfunction "3_3") (pintype "passive"))
    )
    (net (code "113") (name "unconnected-(C40-Pad4)") (class "Default")
      (node (ref "C40") (pin "4") (pinfunction "4_4") (pintype "passive"))
    )
    (net (code "114") (name "unconnected-(C40-Pad5)") (class "Default")
      (node (ref "C40") (pin "5") (pinfunction "5_5") (pintype "passive"))
    )
    (net (code "115") (name "unconnected-(C40-Pad6)") (class "Default")
      (node (ref "C40") (pin "6") (pinfunction "6_6") (pintype "passive"))
    )
    (net (code "116") (name "unconnected-(C40-Pad7)") (class "Default")
      (node (ref "C40") (pin "7") (pinfunction "7_7") (pintype "passive"))
    )
    (net (code "117") (name "unconnected-(C40-Pad8)") (class "Default")
      (node (ref "C40") (pin "8") (pinfunction "8_8") (pintype "passive"))
    )
    (net (code "118") (name "unconnected-(C40-Pad13)") (class "Default")
      (node (ref "C40") (pin "13") (pinfunction "13_13") (pintype "passive"))
    )
    (net (code "119") (name "unconnected-(C40-Pad14)") (class "Default")
      (node (ref "C40") (pin "14") (pinfunction "14_14") (pintype "passive"))
    )
    (net (code "120") (name "unconnected-(C40-Pad15)") (class "Default")
      (node (ref "C40") (pin "15") (pinfunction "15_15") (pintype "passive"))
    )
    (net (code "121") (name "unconnected-(C40-Pad16)") (class "Default")
      (node (ref "C40") (pin "16") (pinfunction "16_16") (pintype "passive"))
    )
    (net (code "122") (name "unconnected-(C40-Pad21)") (class "Default")
      (node (ref "C40") (pin "21") (pinfunction "21_21") (pintype "passive"))
    )
    (net (code "123") (name "unconnected-(C40-Pad22)") (class "Default")
      (node (ref "C40") (pin "22") (pinfunction "22_22") (pintype "passive"))
    )
    (net (code "124") (name "unconnected-(C40-Pad26)") (class "Default")
      (node (ref "C40") (pin "26") (pinfunction "26_26") (pintype "passive"))
    )
    (net (code "125") (name "unconnected-(C40-Pad27)") (class "Default")
      (node (ref "C40") (pin "27") (pinfunction "27_27") (pintype "passive"))
    )
    (net (code "126") (name "unconnected-(C40-Pad29)") (class "Default")
      (node (ref "C40") (pin "29") (pinfunction "29_29") (pintype "passive"))
    )
    (net (code "127") (name "unconnected-(C40-Pad30)") (class "Default")
      (node (ref "C40") (pin "30") (pinfunction "30_30") (pintype "passive"))
    )
    (net (code "128") (name "unconnected-(C40-Pad31)") (class "Default")
      (node (ref "C40") (pin "31") (pinfunction "31_31") (pintype "passive"))
    )
    (net (code "129") (name "unconnected-(C40-Pad32)") (class "Default")
      (node (ref "C40") (pin "32") (pinfunction "32_32") (pintype "passive"))
    )
    (net (code "130") (name "unconnected-(D40-Pad1)") (class "Default")
      (node (ref "D40") (pin "1") (pinfunction "1_1") (pintype "passive"))
    )
    (net (code "131") (name "unconnected-(D40-Pad3)") (class "Default")
      (node (ref "D40") (pin "3") (pinfunction "3_3") (pintype "passive"))
    )
    (net (code "132") (name "unconnected-(D40-Pad5)") (class "Default")
      (node (ref "D40") (pin "5") (pinfunction "5_5") (pintype "passive"))
    )
    (net (code "133") (name "unconnected-(D40-Pad7)") (class "Default")
      (node (ref "D40") (pin "7") (pinfunction "7_7") (pintype "passive"))
    )
    (net (code "134") (name "unconnected-(D40-Pad9)") (class "Default")
      (node (ref "D40") (pin "9") (pinfunction "9_9") (pintype "passive"))
    )
    (net (code "135") (name "unconnected-(D40-Pad11)") (class "Default")
      (node (ref "D40") (pin "11") (pinfunction "11_11") (pintype "passive"))
    )
    (net (code "136") (name "unconnected-(D40-Pad13)") (class "Default")
      (node (ref "D40") (pin "13") (pinfunction "13_13") (pintype "passive"))
    )
    (net (code "137") (name "unconnected-(D40-Pad14)") (class "Default")
      (node (ref "D40") (pin "14") (pinfunction "14_14") (pintype "passive"))
    )
    (net (code "138") (name "unconnected-(D40-Pad15)") (class "Default")
      (node (ref "D40") (pin "15") (pinfunction "15_15") (pintype "passive"))
    )
    (net (code "139") (name "unconnected-(D40-Pad21)") (class "Default")
      (node (ref "D40") (pin "21") (pinfunction "21_21") (pintype "passive"))
    )
    (net (code "140") (name "unconnected-(D40-Pad25)") (class "Default")
      (node (ref "D40") (pin "25") (pinfunction "25_25") (pintype "passive"))
    )
    (net (code "141") (name "unconnected-(D40-Pad27)") (class "Default")
      (node (ref "D40") (pin "27") (pinfunction "27_27") (pintype "passive"))
    )
    (net (code "142") (name "unconnected-(D40-Pad29)") (class "Default")
      (node (ref "D40") (pin "29") (pinfunction "29_29") (pintype "passive"))
    )
    (net (code "143") (name "unconnected-(IC1A-QB-Pad1)") (class "Default")
      (node (ref "IC1") (pin "1") (pinfunction "QB_1") (pintype "tri_state"))
    )
    (net (code "144") (name "unconnected-(IC1A-QC-Pad2)") (class "Default")
      (node (ref "IC1") (pin "2") (pinfunction "QC_2") (pintype "tri_state"))
    )
    (net (code "145") (name "unconnected-(IC1A-QD-Pad3)") (class "Default")
      (node (ref "IC1") (pin "3") (pinfunction "QD_3") (pintype "tri_state"))
    )
    (net (code "146") (name "unconnected-(IC1A-QG-Pad6)") (class "Default")
      (node (ref "IC1") (pin "6") (pinfunction "QG_6") (pintype "tri_state"))
    )
    (net (code "147") (name "unconnected-(IC1A-QH-Pad7)") (class "Default")
      (node (ref "IC1") (pin "7") (pinfunction "QH_7") (pintype "tri_state"))
    )
    (net (code "148") (name "unconnected-(IC2A-QA-Pad15)") (class "Default")
      (node (ref "IC2") (pin "15") (pinfunction "QA_15") (pintype "tri_state"))
    )
    (net (code "149") (name "unconnected-(IC2A-QD-Pad3)") (class "Default")
      (node (ref "IC2") (pin "3") (pinfunction "QD_3") (pintype "tri_state"))
    )
    (net (code "150") (name "unconnected-(IC2A-QE-Pad4)") (class "Default")
      (node (ref "IC2") (pin "4") (pinfunction "QE_4") (pintype "tri_state"))
    )
    (net (code "151") (name "unconnected-(IC2A-QF-Pad5)") (class "Default")
      (node (ref "IC2") (pin "5") (pinfunction "QF_5") (pintype "tri_state"))
    )
    (net (code "152") (name "unconnected-(IC3A-QA-Pad15)") (class "Default")
      (node (ref "IC3") (pin "15") (pinfunction "QA_15") (pintype "tri_state"))
    )
    (net (code "153") (name "unconnected-(IC3A-QB-Pad1)") (class "Default")
      (node (ref "IC3") (pin "1") (pinfunction "QB_1") (pintype "tri_state"))
    )
    (net (code "154") (name "unconnected-(IC3A-QC-Pad2)") (class "Default")
      (node (ref "IC3") (pin "2") (pinfunction "QC_2") (pintype "tri_state"))
    )
    (net (code "155") (name "unconnected-(IC3A-QF-Pad5)") (class "Default")
      (node (ref "IC3") (pin "5") (pinfunction "QF_5") (pintype "tri_state"))
    )
    (net (code "156") (name "unconnected-(IC3A-QG-Pad6)") (class "Default")
      (node (ref "IC3") (pin "6") (pinfunction "QG_6") (pintype "tri_state"))
    )
    (net (code "157") (name "unconnected-(IC3A-QH-Pad7)") (class "Default")
      (node (ref "IC3") (pin "7") (pinfunction "QH_7") (pintype "tri_state"))
    )
    (net (code "158") (name "unconnected-(IC4A-QC-Pad2)") (class "Default")
      (node (ref "IC4") (pin "2") (pinfunction "QC_2") (pintype "tri_state"))
    )
    (net (code "159") (name "unconnected-(IC4A-QD-Pad3)") (class "Default")
      (node (ref "IC4") (pin "3") (pinfunction "QD_3") (pintype "tri_state"))
    )
    (net (code "160") (name "unconnected-(IC4A-QF-Pad5)") (class "Default")
      (node (ref "IC4") (pin "5") (pinfunction "QF_5") (pintype "tri_state"))
    )
    (net (code "161") (name "unconnected-(IC4A-QG-Pad6)") (class "Default")
      (node (ref "IC4") (pin "6") (pinfunction "QG_6") (pintype "tri_state"))
    )
    (net (code "162") (name "unconnected-(IC4A-QH-Pad7)") (class "Default")
      (node (ref "IC4") (pin "7") (pinfunction "QH_7") (pintype "tri_state"))
    )
    (net (code "163") (name "unconnected-(IC8A-QG-Pad6)") (class "Default")
      (node (ref "IC8") (pin "6") (pinfunction "QG_6") (pintype "tri_state"))
    )
    (net (code "164") (name "unconnected-(IC8A-QH-Pad7)") (class "Default")
      (node (ref "IC8") (pin "7") (pinfunction "QH_7") (pintype "tri_state"))
    )
    (net (code "165") (name "unconnected-(IC12A-QG-Pad6)") (class "Default")
      (node (ref "IC12") (pin "6") (pinfunction "QG_6") (pintype "tri_state"))
    )
    (net (code "166") (name "unconnected-(IC12A-QH-Pad7)") (class "Default")
      (node (ref "IC12") (pin "7") (pinfunction "QH_7") (pintype "tri_state"))
    )
    (net (code "167") (name "unconnected-(IC13A-QA-Pad15)") (class "Default")
      (node (ref "IC13") (pin "15") (pinfunction "QA_15") (pintype "tri_state"))
    )
    (net (code "168") (name "unconnected-(IC13A-QB-Pad1)") (class "Default")
      (node (ref "IC13") (pin "1") (pinfunction "QB_1") (pintype "tri_state"))
    )
    (net (code "169") (name "unconnected-(IC13A-QC-Pad2)") (class "Default")
      (node (ref "IC13") (pin "2") (pinfunction "QC_2") (pintype "tri_state"))
    )
    (net (code "170") (name "unconnected-(IC13A-QD-Pad3)") (class "Default")
      (node (ref "IC13") (pin "3") (pinfunction "QD_3") (pintype "tri_state"))
    )
    (net (code "171") (name "unconnected-(IC13A-QE-Pad4)") (class "Default")
      (node (ref "IC13") (pin "4") (pinfunction "QE_4") (pintype "tri_state"))
    )
    (net (code "172") (name "unconnected-(IC14A-QC-Pad2)") (class "Default")
      (node (ref "IC14") (pin "2") (pinfunction "QC_2") (pintype "tri_state"))
    )
    (net (code "173") (name "unconnected-(IC14A-QD-Pad3)") (class "Default")
      (node (ref "IC14") (pin "3") (pinfunction "QD_3") (pintype "tri_state"))
    )
    (net (code "174") (name "unconnected-(IC14A-QE-Pad4)") (class "Default")
      (node (ref "IC14") (pin "4") (pinfunction "QE_4") (pintype "tri_state"))
    )
    (net (code "175") (name "unconnected-(IC14A-QF-Pad5)") (class "Default")
      (node (ref "IC14") (pin "5") (pinfunction "QF_5") (pintype "tri_state"))
    )
    (net (code "176") (name "unconnected-(IC15A-QC-Pad2)") (class "Default")
      (node (ref "IC15") (pin "2") (pinfunction "QC_2") (pintype "tri_state"))
    )
    (net (code "177") (name "unconnected-(IC15A-QE-Pad4)") (class "Default")
      (node (ref "IC15") (pin "4") (pinfunction "QE_4") (pintype "tri_state"))
    )
    (net (code "178") (name "unconnected-(IC15A-QF-Pad5)") (class "Default")
      (node (ref "IC15") (pin "5") (pinfunction "QF_5") (pintype "tri_state"))
    )
    (net (code "179") (name "unconnected-(IC15A-QG-Pad6)") (class "Default")
      (node (ref "IC15") (pin "6") (pinfunction "QG_6") (pintype "tri_state"))
    )
    (net (code "180") (name "unconnected-(IC16A-QG-Pad6)") (class "Default")
      (node (ref "IC16") (pin "6") (pinfunction "QG_6") (pintype "tri_state"))
    )
    (net (code "181") (name "unconnected-(IC16A-QH-Pad7)") (class "Default")
      (node (ref "IC16") (pin "7") (pinfunction "QH_7") (pintype "tri_state"))
    )
    (net (code "182") (name "unconnected-(IC17A-Q-Pad5)") (class "Default")
      (node (ref "IC17") (pin "5") (pinfunction "Q_5") (pintype "output"))
    )
  )
)
